# tacho.net
KiCad netlist of a schematic drawn in EAGLE
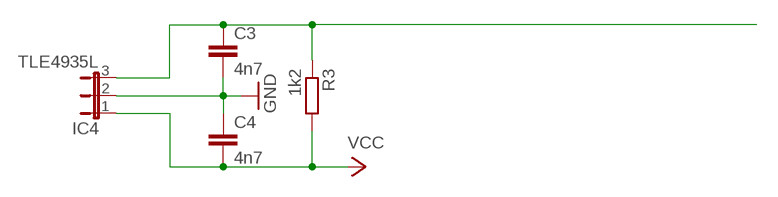
[diagram p0: schematic, sheet 1]

(export (version "E")
  (design (tool "Eeschema 10.0.6"))
  (components
    (comp (ref "C3")
      (value "4n7")
      (footprint "eagle-import:C025-025X050")
      (libsource (lib "eagle-import") (part "C-EU025-025X050"))
    )
    (comp (ref "C4")
      (value "4n7")
      (footprint "eagle-import:C025-025X050")
      (libsource (lib "eagle-import") (part "C-EU025-025X050"))
    )
    (comp (ref "IC4")
      (value "TLE4935L")
      (footprint "eagle-import:JP2")
      (libsource (lib "eagle-import") (part "JP2E"))
    )
    (comp (ref "R3")
      (value "1k2")
      (footprint "eagle-import:0207_10")
      (libsource (lib "eagle-import") (part "R-EU_0207/10"))
    )
  )
  (nets
    (net (code "1") (name "GND") (class "Default")
      (node (ref "C3") (pin "2") (pinfunction "2_2") (pintype "passive"))
      (node (ref "C4") (pin "1") (pinfunction "1_1") (pintype "passive"))
      (node (ref "IC4") (pin "2") (pinfunction "2_2") (pintype "passive"))
    )
    (net (code "2") (name "Net-(C3-Pad1)") (class "Default")
      (node (ref "C3") (pin "1") (pinfunction "1_1") (pintype "passive"))
      (node (ref "IC4") (pin "3") (pinfunction "3_3") (pintype "passive"))
      (node (ref "R3") (pin "1") (pinfunction "1_1") (pintype "passive"))
    )
    (net (code "3") (name "VCC") (class "Default")
      (node (ref "C4") (pin "2") (pinfunction "2_2") (pintype "passive"))
      (node (ref "IC4") (pin "1") (pinfunction "1_1") (pintype "passive"))
      (node (ref "R3") (pin "2") (pinfunction "2_2") (pintype "passive"))
    )
  )
)
